# Component_to_DVI-A_Compact.net
KiCad netlist of a schematic drawn in EAGLE
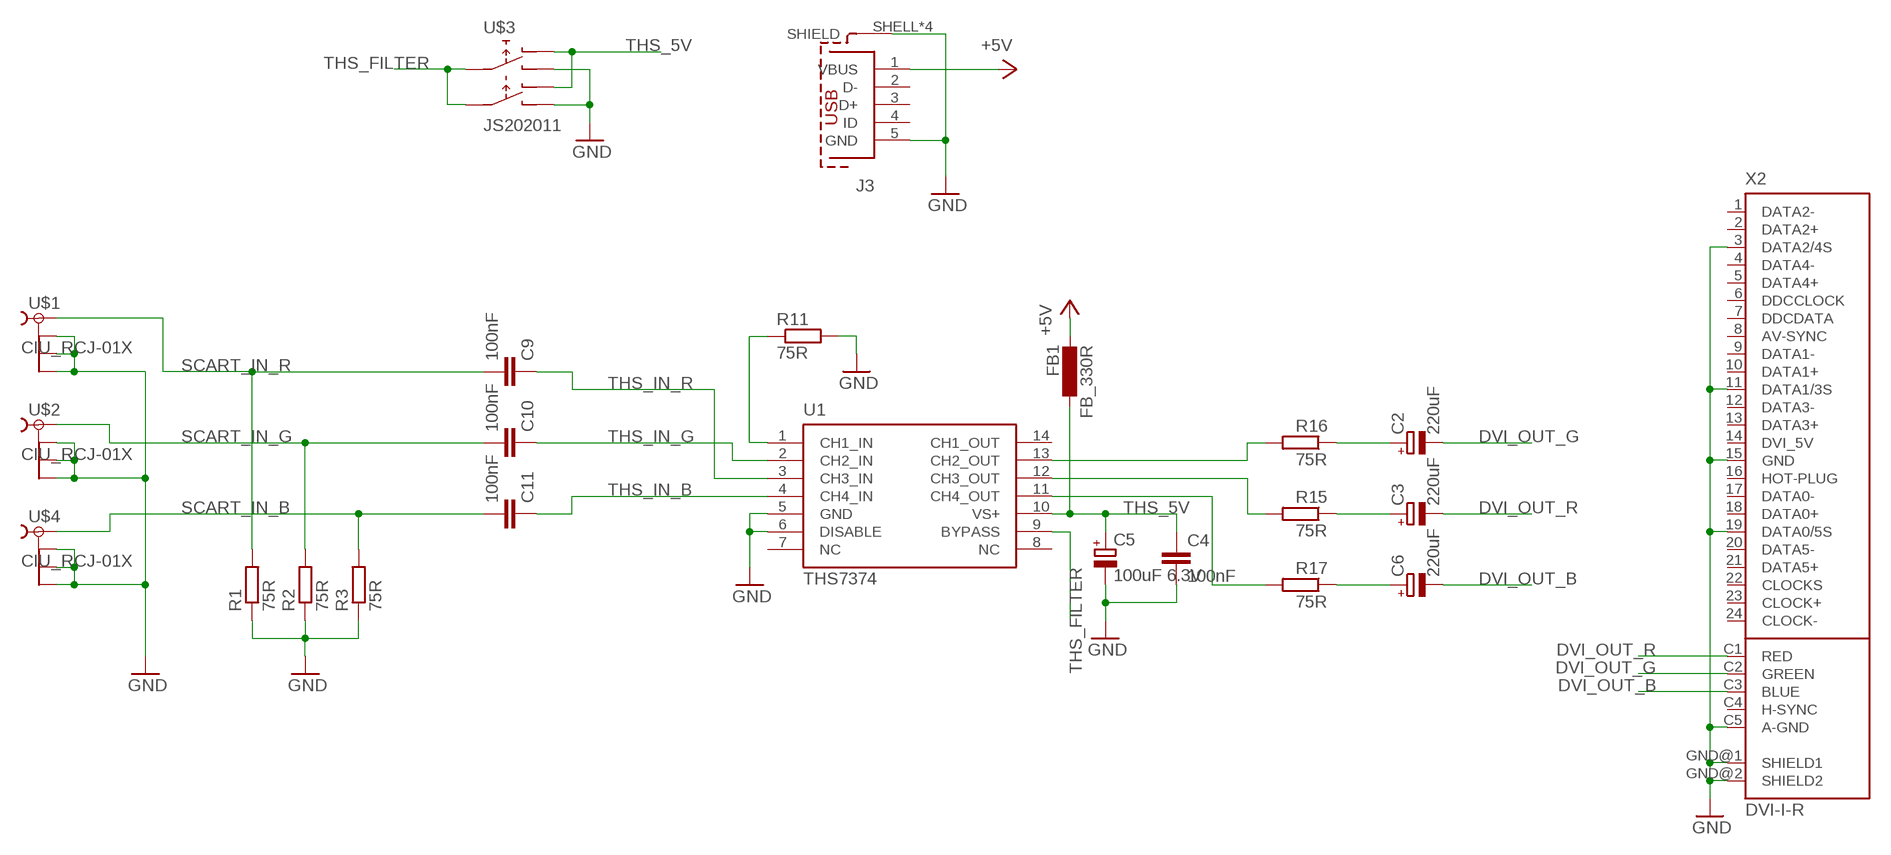
[diagram p0: schematic, sheet 1]

(export (version "E")
  (design (tool "Eeschema 10.0.6"))
  (components
    (comp (ref "C2")
      (value "220uF")
      (footprint "eagle-import:SMC_C")
      (libsource (lib "eagle-import") (part "CPOL-EUSMCC"))
    )
    (comp (ref "C3")
      (value "220uF")
      (footprint "eagle-import:SMC_C")
      (libsource (lib "eagle-import") (part "CPOL-EUSMCC"))
    )
    (comp (ref "C4")
      (value "100nF")
      (footprint "eagle-import:C0603")
      (libsource (lib "eagle-import") (part "C-EUC0603"))
    )
    (comp (ref "C5")
      (value "100uF 6.3V")
      (footprint "eagle-import:PANASONIC_B")
      (libsource (lib "eagle-import") (part "CPOL-EUB"))
    )
    (comp (ref "C6")
      (value "220uF")
      (footprint "eagle-import:SMC_C")
      (libsource (lib "eagle-import") (part "CPOL-EUSMCC"))
    )
    (comp (ref "C9")
      (value "100nF")
      (footprint "eagle-import:C0603")
      (libsource (lib "eagle-import") (part "C-EUC0603"))
    )
    (comp (ref "C10")
      (value "100nF")
      (footprint "eagle-import:C0603")
      (libsource (lib "eagle-import") (part "C-EUC0603"))
    )
    (comp (ref "C11")
      (value "100nF")
      (footprint "eagle-import:C0603")
      (libsource (lib "eagle-import") (part "C-EUC0603"))
    )
    (comp (ref "FB1")
      (value "FB_330R")
      (footprint "eagle-import:L2012C")
      (libsource (lib "eagle-import") (part "L-EUL2012C"))
    )
    (comp (ref "J3")
      (value "629105150521")
      (footprint "eagle-import:629105150521")
      (libsource (lib "eagle-import") (part "629105150521"))
    )
    (comp (ref "R1")
      (value "75R")
      (footprint "eagle-import:R0603")
      (libsource (lib "eagle-import") (part "R-EU_R0603"))
    )
    (comp (ref "R2")
      (value "75R")
      (footprint "eagle-import:R0603")
      (libsource (lib "eagle-import") (part "R-EU_R0603"))
    )
    (comp (ref "R3")
      (value "75R")
      (footprint "eagle-import:R0603")
      (libsource (lib "eagle-import") (part "R-EU_R0603"))
    )
    (comp (ref "R11")
      (value "75R")
      (footprint "eagle-import:R0603")
      (libsource (lib "eagle-import") (part "R-EU_R0603"))
    )
    (comp (ref "R15")
      (value "75R")
      (footprint "eagle-import:R0603")
      (libsource (lib "eagle-import") (part "R-EU_R0603"))
    )
    (comp (ref "R16")
      (value "75R")
      (footprint "eagle-import:R0603")
      (libsource (lib "eagle-import") (part "R-EU_R0603"))
    )
    (comp (ref "R17")
      (value "75R")
      (footprint "eagle-import:R0603")
      (libsource (lib "eagle-import") (part "R-EU_R0603"))
    )
    (comp (ref "U$1")
      (value "CIU_RCJ-01X")
      (footprint "eagle-import:CIU_RCJ-01X")
      (libsource (lib "eagle-import") (part "CIU_RCJ-01X"))
    )
    (comp (ref "U$2")
      (value "CIU_RCJ-01X")
      (footprint "eagle-import:CIU_RCJ-01X")
      (libsource (lib "eagle-import") (part "CIU_RCJ-01X"))
    )
    (comp (ref "U$3")
      (value "JS202011")
      (footprint "eagle-import:JS202011")
      (libsource (lib "eagle-import") (part "JS202011"))
    )
    (comp (ref "U$4")
      (value "CIU_RCJ-01X")
      (footprint "eagle-import:CIU_RCJ-01X")
      (libsource (lib "eagle-import") (part "CIU_RCJ-01X"))
    )
    (comp (ref "U1")
      (value "THS7374")
      (footprint "eagle-import:SO14W")
      (libsource (lib "eagle-import") (part "THS7374"))
    )
    (comp (ref "X2")
      (value "DVI-I-R")
      (footprint "eagle-import:DVI-I-R")
      (libsource (lib "eagle-import") (part "DVI-I-R"))
    )
  )
  (nets
    (net (code "1") (name "+5V") (class "Default")
      (node (ref "FB1") (pin "2") (pinfunction "2_2") (pintype "passive"))
      (node (ref "J3") (pin "1") (pinfunction "VBUS_1") (pintype "passive"))
    )
    (net (code "2") (name "/DVI_5V") (class "Default")
      (node (ref "X2") (pin "14") (pinfunction "DVI_5V_14") (pintype "power_in"))
    )
    (net (code "3") (name "/DVI_OUT_B") (class "Default")
      (node (ref "C6") (pin "-") (pinfunction "-_-") (pintype "passive"))
      (node (ref "X2") (pin "C3") (pinfunction "BLUE_C3") (pintype "passive"))
    )
    (net (code "4") (name "/DVI_OUT_G") (class "Default")
      (node (ref "C2") (pin "-") (pinfunction "-_-") (pintype "passive"))
      (node (ref "X2") (pin "C2") (pinfunction "GREEN_C2") (pintype "passive"))
    )
    (net (code "5") (name "/DVI_OUT_R") (class "Default")
      (node (ref "C3") (pin "-") (pinfunction "-_-") (pintype "passive"))
      (node (ref "X2") (pin "C1") (pinfunction "RED_C1") (pintype "passive"))
    )
    (net (code "6") (name "/SCART_IN_B") (class "Default")
      (node (ref "C11") (pin "2") (pinfunction "2_2") (pintype "passive"))
      (node (ref "R3") (pin "2") (pinfunction "2_2") (pintype "passive"))
      (node (ref "U$4") (pin "1") (pinfunction "1_1") (pintype "passive"))
    )
    (net (code "7") (name "/SCART_IN_G") (class "Default")
      (node (ref "C10") (pin "2") (pinfunction "2_2") (pintype "passive"))
      (node (ref "R2") (pin "2") (pinfunction "2_2") (pintype "passive"))
      (node (ref "U$2") (pin "1") (pinfunction "1_1") (pintype "passive"))
    )
    (net (code "8") (name "/SCART_IN_R") (class "Default")
      (node (ref "C9") (pin "2") (pinfunction "2_2") (pintype "passive"))
      (node (ref "R1") (pin "2") (pinfunction "2_2") (pintype "passive"))
      (node (ref "U$1") (pin "1") (pinfunction "1_1") (pintype "passive"))
    )
    (net (code "9") (name "/THS_5V") (class "Default")
      (node (ref "C4") (pin "1") (pinfunction "1_1") (pintype "passive"))
      (node (ref "C5") (pin "+") (pinfunction "+_+") (pintype "passive"))
      (node (ref "FB1") (pin "1") (pinfunction "1_1") (pintype "passive"))
      (node (ref "U$3") (pin "3") (pinfunction "3_3") (pintype "passive"))
      (node (ref "U$3") (pin "6") (pinfunction "6_6") (pintype "passive"))
      (node (ref "U1") (pin "10") (pinfunction "VS+_10") (pintype "power_in"))
    )
    (net (code "10") (name "/THS_FILTER") (class "Default")
      (node (ref "U$3") (pin "2") (pinfunction "2_2") (pintype "passive"))
      (node (ref "U$3") (pin "5") (pinfunction "5_5") (pintype "passive"))
      (node (ref "U1") (pin "9") (pinfunction "BYPASS_9") (pintype "input"))
    )
    (net (code "11") (name "/THS_IN_B") (class "Default")
      (node (ref "C11") (pin "1") (pinfunction "1_1") (pintype "passive"))
      (node (ref "U1") (pin "4") (pinfunction "CH4_IN_4") (pintype "input"))
    )
    (net (code "12") (name "/THS_IN_G") (class "Default")
      (node (ref "C10") (pin "1") (pinfunction "1_1") (pintype "passive"))
      (node (ref "U1") (pin "2") (pinfunction "CH2_IN_2") (pintype "input"))
    )
    (net (code "13") (name "/THS_IN_R") (class "Default")
      (node (ref "C9") (pin "1") (pinfunction "1_1") (pintype "passive"))
      (node (ref "U1") (pin "3") (pinfunction "CH3_IN_3") (pintype "input"))
    )
    (net (code "14") (name "GND") (class "Default")
      (node (ref "C4") (pin "2") (pinfunction "2_2") (pintype "passive"))
      (node (ref "C5") (pin "-") (pinfunction "-_-") (pintype "passive"))
      (node (ref "J3") (pin "5") (pinfunction "GND_5") (pintype "passive"))
      (node (ref "J3") (pin "SHELL") (pinfunction "SHIELD_SHELL") (pintype "passive"))
      (node (ref "J3") (pin "SHELL1") (pinfunction "SHIELD_SHELL1") (pintype "passive"))
      (node (ref "J3") (pin "SHELL2") (pinfunction "SHIELD_SHELL2") (pintype "passive"))
      (node (ref "J3") (pin "SHELL3") (pinfunction "SHIELD_SHELL3") (pintype "passive"))
      (node (ref "R1") (pin "1") (pinfunction "1_1") (pintype "passive"))
      (node (ref "R11") (pin "2") (pinfunction "2_2") (pintype "passive"))
      (node (ref "R2") (pin "1") (pinfunction "1_1") (pintype "passive"))
      (node (ref "R3") (pin "1") (pinfunction "1_1") (pintype "passive"))
      (node (ref "U$1") (pin "2@1") (pinfunction "2_2@1") (pintype "passive"))
      (node (ref "U$1") (pin "2@2") (pinfunction "3_2@2") (pintype "passive"))
      (node (ref "U$1") (pin "2@3") (pinfunction "4_2@3") (pintype "passive"))
      (node (ref "U$2") (pin "2@1") (pinfunction "2_2@1") (pintype "passive"))
      (node (ref "U$2") (pin "2@2") (pinfunction "3_2@2") (pintype "passive"))
      (node (ref "U$2") (pin "2@3") (pinfunction "4_2@3") (pintype "passive"))
      (node (ref "U$3") (pin "1") (pinfunction "1_1") (pintype "passive"))
      (node (ref "U$3") (pin "4") (pinfunction "4_4") (pintype "passive"))
      (node (ref "U$4") (pin "2@1") (pinfunction "2_2@1") (pintype "passive"))
      (node (ref "U$4") (pin "2@2") (pinfunction "3_2@2") (pintype "passive"))
      (node (ref "U$4") (pin "2@3") (pinfunction "4_2@3") (pintype "passive"))
      (node (ref "U1") (pin "5") (pinfunction "GND_5") (pintype "power_in"))
      (node (ref "U1") (pin "6") (pinfunction "DISABLE_6") (pintype "input"))
      (node (ref "X2") (pin "11") (pinfunction "DATA1/3S_11") (pintype "passive"))
      (node (ref "X2") (pin "15") (pinfunction "GND_15") (pintype "power_in"))
      (node (ref "X2") (pin "19") (pinfunction "DATA0/5S_19") (pintype "passive"))
      (node (ref "X2") (pin "3") (pinfunction "DATA2/4S_3") (pintype "passive"))
      (node (ref "X2") (pin "C5") (pinfunction "A-GND_C5") (pintype "power_in"))
      (node (ref "X2") (pin "GND@1") (pinfunction "SHIELD1_GND@1") (pintype "passive"))
      (node (ref "X2") (pin "GND@2") (pinfunction "SHIELD2_GND@2") (pintype "passive"))
    )
    (net (code "15") (name "Net-(C2-Pad+)") (class "Default")
      (node (ref "C2") (pin "+") (pinfunction "+_+") (pintype "passive"))
      (node (ref "R16") (pin "1") (pinfunction "1_1") (pintype "passive"))
    )
    (net (code "16") (name "Net-(C3-Pad+)") (class "Default")
      (node (ref "C3") (pin "+") (pinfunction "+_+") (pintype "passive"))
      (node (ref "R15") (pin "1") (pinfunction "1_1") (pintype "passive"))
    )
    (net (code "17") (name "Net-(C6-Pad+)") (class "Default")
      (node (ref "C6") (pin "+") (pinfunction "+_+") (pintype "passive"))
      (node (ref "R17") (pin "1") (pinfunction "1_1") (pintype "passive"))
    )
    (net (code "18") (name "Net-(U1-CH1_IN)") (class "Default")
      (node (ref "R11") (pin "1") (pinfunction "1_1") (pintype "passive"))
      (node (ref "U1") (pin "1") (pinfunction "CH1_IN_1") (pintype "input"))
    )
    (net (code "19") (name "Net-(U1-CH2_OUT)") (class "Default")
      (node (ref "R16") (pin "2") (pinfunction "2_2") (pintype "passive"))
      (node (ref "U1") (pin "13") (pinfunction "CH2_OUT_13") (pintype "output"))
    )
    (net (code "20") (name "Net-(U1-CH3_OUT)") (class "Default")
      (node (ref "R15") (pin "2") (pinfunction "2_2") (pintype "passive"))
      (node (ref "U1") (pin "12") (pinfunction "CH3_OUT_12") (pintype "output"))
    )
    (net (code "21") (name "Net-(U1-CH4_OUT)") (class "Default")
      (node (ref "R17") (pin "2") (pinfunction "2_2") (pintype "passive"))
      (node (ref "U1") (pin "11") (pinfunction "CH4_OUT_11") (pintype "output"))
    )
    (net (code "22") (name "unconnected-(J3-D+-Pad3)") (class "Default")
      (node (ref "J3") (pin "3") (pinfunction "D+_3") (pintype "passive"))
    )
    (net (code "23") (name "unconnected-(J3-D--Pad2)") (class "Default")
      (node (ref "J3") (pin "2") (pinfunction "D-_2") (pintype "passive"))
    )
    (net (code "24") (name "unconnected-(J3-ID-Pad4)") (class "Default")
      (node (ref "J3") (pin "4") (pinfunction "ID_4") (pintype "passive"))
    )
    (net (code "25") (name "unconnected-(U1-CH1_OUT-Pad14)") (class "Default")
      (node (ref "U1") (pin "14") (pinfunction "CH1_OUT_14") (pintype "output"))
    )
    (net (code "26") (name "unconnected-(U1-NC-Pad7)") (class "Default")
      (node (ref "U1") (pin "7") (pinfunction "NC_7") (pintype "no_connect"))
    )
    (net (code "27") (name "unconnected-(U1-NC-Pad8)") (class "Default")
      (node (ref "U1") (pin "8") (pinfunction "NC_8") (pintype "no_connect"))
    )
    (net (code "28") (name "unconnected-(X2B-AV-SYNC-Pad8)") (class "Default")
      (node (ref "X2") (pin "8") (pinfunction "AV-SYNC_8") (pintype "passive"))
    )
    (net (code "29") (name "unconnected-(X2B-CLOCK+-Pad23)") (class "Default")
      (node (ref "X2") (pin "23") (pinfunction "CLOCK+_23") (pintype "passive"))
    )
    (net (code "30") (name "unconnected-(X2B-CLOCK--Pad24)") (class "Default")
      (node (ref "X2") (pin "24") (pinfunction "CLOCK-_24") (pintype "passive"))
    )
    (net (code "31") (name "unconnected-(X2B-CLOCKS-Pad22)") (class "Default")
      (node (ref "X2") (pin "22") (pinfunction "CLOCKS_22") (pintype "passive"))
    )
    (net (code "32") (name "unconnected-(X2B-DATA0+-Pad18)") (class "Default")
      (node (ref "X2") (pin "18") (pinfunction "DATA0+_18") (pintype "passive"))
    )
    (net (code "33") (name "unconnected-(X2B-DATA0--Pad17)") (class "Default")
      (node (ref "X2") (pin "17") (pinfunction "DATA0-_17") (pintype "passive"))
    )
    (net (code "34") (name "unconnected-(X2B-DATA1+-Pad10)") (class "Default")
      (node (ref "X2") (pin "10") (pinfunction "DATA1+_10") (pintype "passive"))
    )
    (net (code "35") (name "unconnected-(X2B-DATA1--Pad9)") (class "Default")
      (node (ref "X2") (pin "9") (pinfunction "DATA1-_9") (pintype "passive"))
    )
    (net (code "36") (name "unconnected-(X2B-DATA2+-Pad2)") (class "Default")
      (node (ref "X2") (pin "2") (pinfunction "DATA2+_2") (pintype "passive"))
    )
    (net (code "37") (name "unconnected-(X2B-DATA2--Pad1)") (class "Default")
      (node (ref "X2") (pin "1") (pinfunction "DATA2-_1") (pintype "passive"))
    )
    (net (code "38") (name "unconnected-(X2B-DATA3+-Pad13)") (class "Default")
      (node (ref "X2") (pin "13") (pinfunction "DATA3+_13") (pintype "passive"))
    )
    (net (code "39") (name "unconnected-(X2B-DATA3--Pad12)") (class "Default")
      (node (ref "X2") (pin "12") (pinfunction "DATA3-_12") (pintype "passive"))
    )
    (net (code "40") (name "unconnected-(X2B-DATA4+-Pad5)") (class "Default")
      (node (ref "X2") (pin "5") (pinfunction "DATA4+_5") (pintype "passive"))
    )
    (net (code "41") (name "unconnected-(X2B-DATA4--Pad4)") (class "Default")
      (node (ref "X2") (pin "4") (pinfunction "DATA4-_4") (pintype "passive"))
    )
    (net (code "42") (name "unconnected-(X2B-DATA5+-Pad21)") (class "Default")
      (node (ref "X2") (pin "21") (pinfunction "DATA5+_21") (pintype "passive"))
    )
    (net (code "43") (name "unconnected-(X2B-DATA5--Pad20)") (class "Default")
      (node (ref "X2") (pin "20") (pinfunction "DATA5-_20") (pintype "passive"))
    )
    (net (code "44") (name "unconnected-(X2B-DDCCLOCK-Pad6)") (class "Default")
      (node (ref "X2") (pin "6") (pinfunction "DDCCLOCK_6") (pintype "passive"))
    )
    (net (code "45") (name "unconnected-(X2B-DDCDATA-Pad7)") (class "Default")
      (node (ref "X2") (pin "7") (pinfunction "DDCDATA_7") (pintype "passive"))
    )
    (net (code "46") (name "unconnected-(X2B-H-SYNC-PadC4)") (class "Default")
      (node (ref "X2") (pin "C4") (pinfunction "H-SYNC_C4") (pintype "passive"))
    )
    (net (code "47") (name "unconnected-(X2B-HOT-PLUG-Pad16)") (class "Default")
      (node (ref "X2") (pin "16") (pinfunction "HOT-PLUG_16") (pintype "passive"))
    )
  )
)
